# lap_counter_V1_1.net
KiCad netlist of a schematic drawn in EAGLE
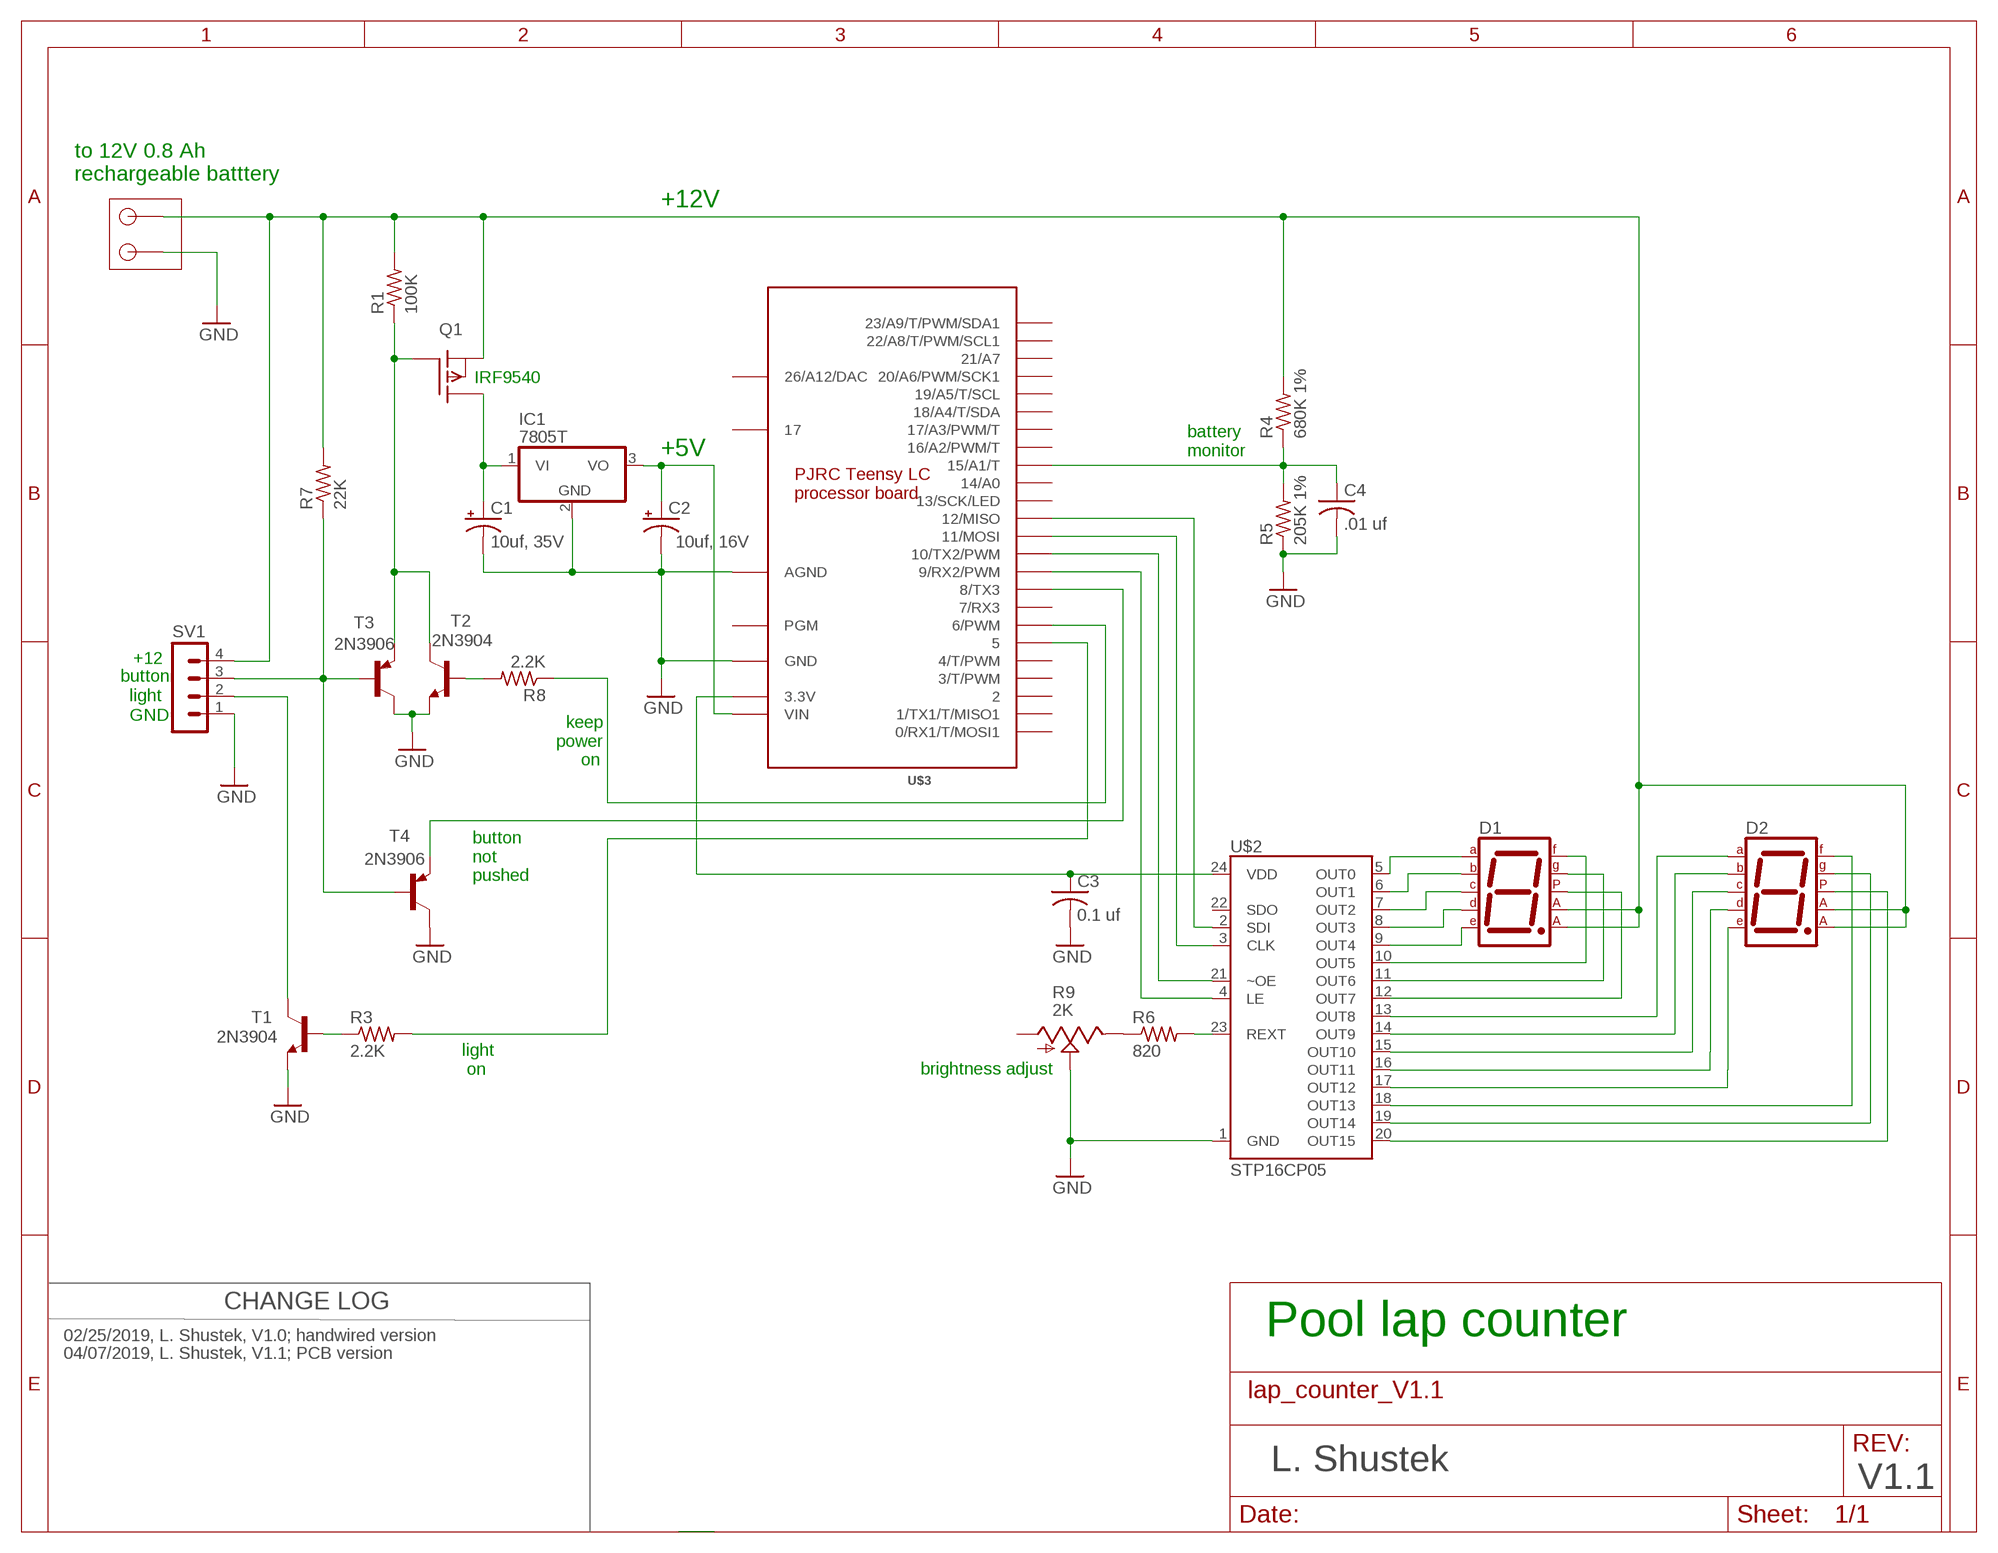
[diagram p0: schematic, sheet 1]

(export (version "E")
  (design (tool "Eeschema 10.0.6"))
  (components
    (comp (ref "C1")
      (value "10uf, 35V")
      (footprint "eagle-import:E2,5-6")
      (libsource (lib "eagle-import") (part "CPOL-USE2.5-6"))
    )
    (comp (ref "C2")
      (value "10uf, 16V")
      (footprint "eagle-import:E2,5-6")
      (libsource (lib "eagle-import") (part "CPOL-USE2.5-6"))
    )
    (comp (ref "C3")
      (value "0.1 uf")
      (footprint "eagle-import:C025-030X050")
      (libsource (lib "eagle-import") (part "C-US025-030X050"))
    )
    (comp (ref "C4")
      (value ".01 uf")
      (footprint "eagle-import:C025-030X050")
      (libsource (lib "eagle-import") (part "C-US025-030X050"))
    )
    (comp (ref "D1")
      (value "7SEG-CA")
      (footprint "eagle-import:7SEG-13")
      (libsource (lib "eagle-import") (part "7SEG-CA"))
    )
    (comp (ref "D2")
      (value "7SEG-CA")
      (footprint "eagle-import:7SEG-13")
      (libsource (lib "eagle-import") (part "7SEG-CA"))
    )
    (comp (ref "IC1")
      (value "7805T")
      (footprint "eagle-import:TO220H")
      (libsource (lib "eagle-import") (part "78T05"))
    )
    (comp (ref "Q1")
      (value "IRF9530")
      (footprint "eagle-import:TO220")
      (libsource (lib "eagle-import") (part "IRF9530"))
    )
    (comp (ref "R1")
      (value "100K")
      (footprint "eagle-import:0207_10")
      (libsource (lib "eagle-import") (part "R-US_0207/10"))
    )
    (comp (ref "R3")
      (value "2.2K")
      (footprint "eagle-import:0207_10")
      (libsource (lib "eagle-import") (part "R-US_0207/10"))
    )
    (comp (ref "R4")
      (value "680K 1%")
      (footprint "eagle-import:0207_10")
      (libsource (lib "eagle-import") (part "R-US_0207/10"))
    )
    (comp (ref "R5")
      (value "205K 1%")
      (footprint "eagle-import:0207_10")
      (libsource (lib "eagle-import") (part "R-US_0207/10"))
    )
    (comp (ref "R6")
      (value "820")
      (footprint "eagle-import:0207_10")
      (libsource (lib "eagle-import") (part "R-US_0207/10"))
    )
    (comp (ref "R7")
      (value "22K")
      (footprint "eagle-import:0207_10")
      (libsource (lib "eagle-import") (part "R-US_0207/10"))
    )
    (comp (ref "R8")
      (value "2.2K")
      (footprint "eagle-import:0207_10")
      (libsource (lib "eagle-import") (part "R-US_0207/10"))
    )
    (comp (ref "R9")
      (value "2K")
      (footprint "eagle-import:B25P")
      (libsource (lib "eagle-import") (part "TRIM_US-B25P"))
    )
    (comp (ref "SV1")
      (value "MA04-1")
      (footprint "eagle-import:MA04-1")
      (libsource (lib "eagle-import") (part "MA04-1"))
    )
    (comp (ref "T1")
      (value "2N3904")
      (footprint "eagle-import:TO92-EBC-OVAL")
      (libsource (lib "eagle-import") (part "2N2222"))
    )
    (comp (ref "T2")
      (value "2N3904")
      (footprint "eagle-import:TO92-EBC-OVAL")
      (libsource (lib "eagle-import") (part "2N2222"))
    )
    (comp (ref "T3")
      (value "2N3906")
      (footprint "eagle-import:TO92-EBC-OVAL")
      (libsource (lib "eagle-import") (part "2N2907"))
    )
    (comp (ref "T4")
      (value "2N3906")
      (footprint "eagle-import:TO92-EBC-OVAL")
      (libsource (lib "eagle-import") (part "2N2907"))
    )
    (comp (ref "U$1")
      (value "CONNECTOR-2PIN")
      (footprint "eagle-import:CONNECTOR-2PIN-5MM")
      (libsource (lib "eagle-import") (part "CONNECTOR-2PIN"))
    )
    (comp (ref "U$2")
      (value "STP16CP05")
      (footprint "eagle-import:SO-24DW")
      (libsource (lib "eagle-import") (part "STP16CP05"))
    )
    (comp (ref "U$3")
      (value "TEENSY_LC_OUTER_ROW")
      (footprint "eagle-import:TEENSY3-OUTER_ROW")
      (libsource (lib "eagle-import") (part "TEENSY_LC_OUTER_ROW"))
    )
  )
  (nets
    (net (code "1") (name "/26{slash}A12{slash}DAC") (class "Default")
      (node (ref "U$3") (pin "RESET/DAC") (pinfunction "26/A12/DAC_RESET/DAC") (pintype "power_in"))
    )
    (net (code "2") (name "GND") (class "Default")
      (node (ref "C1") (pin "-") (pinfunction "-_-") (pintype "passive"))
      (node (ref "C2") (pin "-") (pinfunction "-_-") (pintype "passive"))
      (node (ref "C3") (pin "2") (pinfunction "2_2") (pintype "passive"))
      (node (ref "C4") (pin "2") (pinfunction "2_2") (pintype "passive"))
      (node (ref "IC1") (pin "2") (pinfunction "GND_2") (pintype "passive"))
      (node (ref "R5") (pin "1") (pinfunction "1_1") (pintype "passive"))
      (node (ref "R9") (pin "S") (pinfunction "S_S") (pintype "passive"))
      (node (ref "SV1") (pin "1") (pinfunction "1_1") (pintype "passive"))
      (node (ref "T1") (pin "E") (pinfunction "E_E") (pintype "passive"))
      (node (ref "T2") (pin "E") (pinfunction "E_E") (pintype "passive"))
      (node (ref "T3") (pin "C") (pinfunction "C_C") (pintype "passive"))
      (node (ref "T4") (pin "C") (pinfunction "C_C") (pintype "passive"))
      (node (ref "U$1") (pin "P$1") (pinfunction "P$1_P$1") (pintype "bidirectional"))
      (node (ref "U$2") (pin "1") (pinfunction "GND_1") (pintype "bidirectional"))
      (node (ref "U$3") (pin "AGND") (pinfunction "AGND_AGND") (pintype "power_in"))
      (node (ref "U$3") (pin "GND") (pinfunction "GND_GND") (pintype "power_in"))
      (node (ref "U$3") (pin "GND1") (pinfunction "GND_GND1") (pintype "power_in"))
    )
    (net (code "3") (name "Net-(D1-A)") (class "Default")
      (node (ref "D1") (pin "7") (pinfunction "A_7") (pintype "passive"))
      (node (ref "U$2") (pin "5") (pinfunction "OUT0_5") (pintype "bidirectional"))
    )
    (net (code "4") (name "Net-(D1-B)") (class "Default")
      (node (ref "D1") (pin "6") (pinfunction "B_6") (pintype "passive"))
      (node (ref "U$2") (pin "6") (pinfunction "OUT1_6") (pintype "bidirectional"))
    )
    (net (code "5") (name "Net-(D1-C)") (class "Default")
      (node (ref "D1") (pin "4") (pinfunction "C_4") (pintype "passive"))
      (node (ref "U$2") (pin "7") (pinfunction "OUT2_7") (pintype "bidirectional"))
    )
    (net (code "6") (name "Net-(D1-CA1)") (class "Default")
      (node (ref "D1") (pin "3") (pinfunction "CA1_3") (pintype "passive"))
      (node (ref "D1") (pin "8") (pinfunction "CA2_8") (pintype "passive"))
      (node (ref "D2") (pin "3") (pinfunction "CA1_3") (pintype "passive"))
      (node (ref "D2") (pin "8") (pinfunction "CA2_8") (pintype "passive"))
      (node (ref "Q1") (pin "3") (pinfunction "S_3") (pintype "passive"))
      (node (ref "R1") (pin "2") (pinfunction "2_2") (pintype "passive"))
      (node (ref "R4") (pin "2") (pinfunction "2_2") (pintype "passive"))
      (node (ref "R7") (pin "2") (pinfunction "2_2") (pintype "passive"))
      (node (ref "SV1") (pin "4") (pinfunction "4_4") (pintype "passive"))
      (node (ref "U$1") (pin "P$2") (pinfunction "P$2_P$2") (pintype "bidirectional"))
    )
    (net (code "7") (name "Net-(D1-D)") (class "Default")
      (node (ref "D1") (pin "2") (pinfunction "D_2") (pintype "passive"))
      (node (ref "U$2") (pin "8") (pinfunction "OUT3_8") (pintype "bidirectional"))
    )
    (net (code "8") (name "Net-(D1-DP)") (class "Default")
      (node (ref "D1") (pin "5") (pinfunction "DP_5") (pintype "passive"))
      (node (ref "U$2") (pin "12") (pinfunction "OUT7_12") (pintype "bidirectional"))
    )
    (net (code "9") (name "Net-(D1-E)") (class "Default")
      (node (ref "D1") (pin "1") (pinfunction "E_1") (pintype "passive"))
      (node (ref "U$2") (pin "9") (pinfunction "OUT4_9") (pintype "bidirectional"))
    )
    (net (code "10") (name "Net-(D1-F)") (class "Default")
      (node (ref "D1") (pin "9") (pinfunction "F_9") (pintype "passive"))
      (node (ref "U$2") (pin "10") (pinfunction "OUT5_10") (pintype "bidirectional"))
    )
    (net (code "11") (name "Net-(D1-G)") (class "Default")
      (node (ref "D1") (pin "10") (pinfunction "G_10") (pintype "passive"))
      (node (ref "U$2") (pin "11") (pinfunction "OUT6_11") (pintype "bidirectional"))
    )
    (net (code "12") (name "Net-(D2-A)") (class "Default")
      (node (ref "D2") (pin "7") (pinfunction "A_7") (pintype "passive"))
      (node (ref "U$2") (pin "13") (pinfunction "OUT8_13") (pintype "bidirectional"))
    )
    (net (code "13") (name "Net-(D2-B)") (class "Default")
      (node (ref "D2") (pin "6") (pinfunction "B_6") (pintype "passive"))
      (node (ref "U$2") (pin "14") (pinfunction "OUT9_14") (pintype "bidirectional"))
    )
    (net (code "14") (name "Net-(D2-C)") (class "Default")
      (node (ref "D2") (pin "4") (pinfunction "C_4") (pintype "passive"))
      (node (ref "U$2") (pin "15") (pinfunction "OUT10_15") (pintype "bidirectional"))
    )
    (net (code "15") (name "Net-(D2-D)") (class "Default")
      (node (ref "D2") (pin "2") (pinfunction "D_2") (pintype "passive"))
      (node (ref "U$2") (pin "16") (pinfunction "OUT11_16") (pintype "bidirectional"))
    )
    (net (code "16") (name "Net-(D2-DP)") (class "Default")
      (node (ref "D2") (pin "5") (pinfunction "DP_5") (pintype "passive"))
      (node (ref "U$2") (pin "20") (pinfunction "OUT15_20") (pintype "bidirectional"))
    )
    (net (code "17") (name "Net-(D2-E)") (class "Default")
      (node (ref "D2") (pin "1") (pinfunction "E_1") (pintype "passive"))
      (node (ref "U$2") (pin "17") (pinfunction "OUT12_17") (pintype "bidirectional"))
    )
    (net (code "18") (name "Net-(D2-F)") (class "Default")
      (node (ref "D2") (pin "9") (pinfunction "F_9") (pintype "passive"))
      (node (ref "U$2") (pin "18") (pinfunction "OUT13_18") (pintype "bidirectional"))
    )
    (net (code "19") (name "Net-(D2-G)") (class "Default")
      (node (ref "D2") (pin "10") (pinfunction "G_10") (pintype "passive"))
      (node (ref "U$2") (pin "19") (pinfunction "OUT14_19") (pintype "bidirectional"))
    )
    (net (code "20") (name "Net-(IC1-VI)") (class "Default")
      (node (ref "C1") (pin "+") (pinfunction "+_+") (pintype "passive"))
      (node (ref "IC1") (pin "1") (pinfunction "VI_1") (pintype "input"))
      (node (ref "Q1") (pin "2") (pinfunction "D_2") (pintype "passive"))
    )
    (net (code "21") (name "Net-(IC1-VO)") (class "Default")
      (node (ref "C2") (pin "+") (pinfunction "+_+") (pintype "passive"))
      (node (ref "IC1") (pin "3") (pinfunction "VO_3") (pintype "passive"))
      (node (ref "U$3") (pin "VIN") (pinfunction "VIN_VIN") (pintype "power_in"))
    )
    (net (code "22") (name "Net-(Q1-G)") (class "Default")
      (node (ref "Q1") (pin "1") (pinfunction "G_1") (pintype "passive"))
      (node (ref "R1") (pin "1") (pinfunction "1_1") (pintype "passive"))
      (node (ref "T2") (pin "C") (pinfunction "C_C") (pintype "passive"))
      (node (ref "T3") (pin "E") (pinfunction "E_E") (pintype "passive"))
    )
    (net (code "23") (name "Net-(R3-Pad1)") (class "Default")
      (node (ref "R3") (pin "1") (pinfunction "1_1") (pintype "passive"))
      (node (ref "T1") (pin "B") (pinfunction "B_B") (pintype "passive"))
    )
    (net (code "24") (name "Net-(R3-Pad2)") (class "Default")
      (node (ref "R3") (pin "2") (pinfunction "2_2") (pintype "passive"))
      (node (ref "U$3") (pin "5") (pinfunction "5_5") (pintype "bidirectional"))
    )
    (net (code "25") (name "Net-(R6-Pad1)") (class "Default")
      (node (ref "R6") (pin "1") (pinfunction "1_1") (pintype "passive"))
      (node (ref "R9") (pin "E") (pinfunction "E_E") (pintype "passive"))
    )
    (net (code "26") (name "Net-(R7-Pad1)") (class "Default")
      (node (ref "R7") (pin "1") (pinfunction "1_1") (pintype "passive"))
      (node (ref "SV1") (pin "3") (pinfunction "3_3") (pintype "passive"))
      (node (ref "T3") (pin "B") (pinfunction "B_B") (pintype "passive"))
      (node (ref "T4") (pin "B") (pinfunction "B_B") (pintype "passive"))
    )
    (net (code "27") (name "Net-(R8-Pad2)") (class "Default")
      (node (ref "R8") (pin "2") (pinfunction "2_2") (pintype "passive"))
      (node (ref "T2") (pin "B") (pinfunction "B_B") (pintype "passive"))
    )
    (net (code "28") (name "Net-(SV1-Pad2)") (class "Default")
      (node (ref "SV1") (pin "2") (pinfunction "2_2") (pintype "passive"))
      (node (ref "T1") (pin "C") (pinfunction "C_C") (pintype "passive"))
    )
    (net (code "29") (name "Net-(U$2-CLK)") (class "Default")
      (node (ref "U$2") (pin "3") (pinfunction "CLK_3") (pintype "bidirectional"))
      (node (ref "U$3") (pin "11") (pinfunction "11/MOSI_11") (pintype "bidirectional"))
    )
    (net (code "30") (name "Net-(U$2-LE)") (class "Default")
      (node (ref "U$2") (pin "4") (pinfunction "LE_4") (pintype "bidirectional"))
      (node (ref "U$3") (pin "9") (pinfunction "9/RX2/PWM_9") (pintype "bidirectional"))
    )
    (net (code "31") (name "Net-(U$2-REXT)") (class "Default")
      (node (ref "R6") (pin "2") (pinfunction "2_2") (pintype "passive"))
      (node (ref "U$2") (pin "23") (pinfunction "REXT_23") (pintype "bidirectional"))
    )
    (net (code "32") (name "Net-(U$2-SDI)") (class "Default")
      (node (ref "U$2") (pin "2") (pinfunction "SDI_2") (pintype "bidirectional"))
      (node (ref "U$3") (pin "12") (pinfunction "12/MISO_12") (pintype "bidirectional"))
    )
    (net (code "33") (name "Net-(U$2-VDD)") (class "Default")
      (node (ref "C3") (pin "1") (pinfunction "1_1") (pintype "passive"))
      (node (ref "U$2") (pin "24") (pinfunction "VDD_24") (pintype "bidirectional"))
      (node (ref "U$3") (pin "3.3V") (pinfunction "3.3V_3.3V") (pintype "power_in"))
      (node (ref "U$3") (pin "3.3V1") (pinfunction "3.3V_3.3V1") (pintype "power_in"))
    )
    (net (code "34") (name "Net-(U$2-~{OE})") (class "Default")
      (node (ref "U$2") (pin "21") (pinfunction "~{OE}_21") (pintype "bidirectional"))
      (node (ref "U$3") (pin "10") (pinfunction "10/TX2/PWM_10") (pintype "bidirectional"))
    )
    (net (code "35") (name "Net-(U$3-6{slash}PWM)") (class "Default")
      (node (ref "R8") (pin "1") (pinfunction "1_1") (pintype "passive"))
      (node (ref "U$3") (pin "6") (pinfunction "6/PWM_6") (pintype "bidirectional"))
    )
    (net (code "36") (name "Net-(U$3-8{slash}TX3)") (class "Default")
      (node (ref "T4") (pin "E") (pinfunction "E_E") (pintype "passive"))
      (node (ref "U$3") (pin "8") (pinfunction "8/TX3_8") (pintype "bidirectional"))
    )
    (net (code "37") (name "Net-(U$3-15{slash}A1{slash}T)") (class "Default")
      (node (ref "C4") (pin "1") (pinfunction "1_1") (pintype "passive"))
      (node (ref "R4") (pin "1") (pinfunction "1_1") (pintype "passive"))
      (node (ref "R5") (pin "2") (pinfunction "2_2") (pintype "passive"))
      (node (ref "U$3") (pin "15/A1") (pinfunction "15/A1/T_15/A1") (pintype "bidirectional"))
    )
    (net (code "38") (name "unconnected-(R9-PadA)") (class "Default")
      (node (ref "R9") (pin "A") (pinfunction "A_A") (pintype "passive"))
    )
    (net (code "39") (name "unconnected-(U$2-SDO-Pad22)") (class "Default")
      (node (ref "U$2") (pin "22") (pinfunction "SDO_22") (pintype "bidirectional"))
    )
    (net (code "40") (name "unconnected-(U$3-0{slash}RX1{slash}T{slash}MOSI1-Pad0)") (class "Default")
      (node (ref "U$3") (pin "0") (pinfunction "0/RX1/T/MOSI1_0") (pintype "bidirectional"))
    )
    (net (code "41") (name "unconnected-(U$3-1{slash}TX1{slash}T{slash}MISO1-Pad1)") (class "Default")
      (node (ref "U$3") (pin "1") (pinfunction "1/TX1/T/MISO1_1") (pintype "bidirectional"))
    )
    (net (code "42") (name "unconnected-(U$3-3{slash}T{slash}PWM-Pad3)") (class "Default")
      (node (ref "U$3") (pin "3") (pinfunction "3/T/PWM_3") (pintype "bidirectional"))
    )
    (net (code "43") (name "unconnected-(U$3-4{slash}T{slash}PWM-Pad4)") (class "Default")
      (node (ref "U$3") (pin "4") (pinfunction "4/T/PWM_4") (pintype "bidirectional"))
    )
    (net (code "44") (name "unconnected-(U$3-7{slash}RX3-Pad7)") (class "Default")
      (node (ref "U$3") (pin "7") (pinfunction "7/RX3_7") (pintype "bidirectional"))
    )
    (net (code "45") (name "unconnected-(U$3-13{slash}SCK{slash}LED-Pad13)") (class "Default")
      (node (ref "U$3") (pin "13") (pinfunction "13/SCK/LED_13") (pintype "bidirectional"))
    )
    (net (code "46") (name "unconnected-(U$3-16{slash}A2{slash}PWM{slash}T-Pad16{slash}A2)") (class "Default")
      (node (ref "U$3") (pin "16/A2") (pinfunction "16/A2/PWM/T_16/A2") (pintype "bidirectional"))
    )
    (net (code "47") (name "unconnected-(U$3-17-PadVBAT)") (class "Default")
      (node (ref "U$3") (pin "VBAT") (pinfunction "17_VBAT") (pintype "bidirectional"))
    )
    (net (code "48") (name "unconnected-(U$3-17{slash}A3{slash}PWM{slash}T-Pad17{slash}A3)") (class "Default")
      (node (ref "U$3") (pin "17/A3") (pinfunction "17/A3/PWM/T_17/A3") (pintype "bidirectional"))
    )
    (net (code "49") (name "unconnected-(U$3-18{slash}A4{slash}T{slash}SDA-Pad18{slash}A4)") (class "Default")
      (node (ref "U$3") (pin "18/A4") (pinfunction "18/A4/T/SDA_18/A4") (pintype "bidirectional"))
    )
    (net (code "50") (name "unconnected-(U$3-19{slash}A5{slash}T{slash}SCL-Pad19{slash}A5)") (class "Default")
      (node (ref "U$3") (pin "19/A5") (pinfunction "19/A5/T/SCL_19/A5") (pintype "bidirectional"))
    )
    (net (code "51") (name "unconnected-(U$3-20{slash}A6{slash}PWM{slash}SCK1-Pad20{slash}A6)") (class "Default")
      (node (ref "U$3") (pin "20/A6") (pinfunction "20/A6/PWM/SCK1_20/A6") (pintype "bidirectional"))
    )
    (net (code "52") (name "unconnected-(U$3-22{slash}A8{slash}T{slash}PWM{slash}SCL1-Pad22{slash}A8)") (class "Default")
      (node (ref "U$3") (pin "22/A8") (pinfunction "22/A8/T/PWM/SCL1_22/A8") (pintype "bidirectional"))
    )
    (net (code "53") (name "unconnected-(U$3-23{slash}A9{slash}T{slash}PWM{slash}SDA1-Pad23{slash}A9)") (class "Default")
      (node (ref "U$3") (pin "23/A9") (pinfunction "23/A9/T/PWM/SDA1_23/A9") (pintype "bidirectional"))
    )
    (net (code "54") (name "unconnected-(U$3-Pad2)") (class "Default")
      (node (ref "U$3") (pin "2") (pinfunction "2_2") (pintype "bidirectional"))
    )
    (net (code "55") (name "unconnected-(U$3-Pad14{slash}A0)") (class "Default")
      (node (ref "U$3") (pin "14/A0") (pinfunction "14/A0_14/A0") (pintype "bidirectional"))
    )
    (net (code "56") (name "unconnected-(U$3-Pad21{slash}A7)") (class "Default")
      (node (ref "U$3") (pin "21/A7") (pinfunction "21/A7_21/A7") (pintype "bidirectional"))
    )
    (net (code "57") (name "unconnected-(U$3-PadPGM)") (class "Default")
      (node (ref "U$3") (pin "PGM") (pinfunction "PGM_PGM") (pintype "bidirectional"))
    )
  )
)
